# ERA-3SM.net
KiCad netlist of a schematic drawn in EAGLE
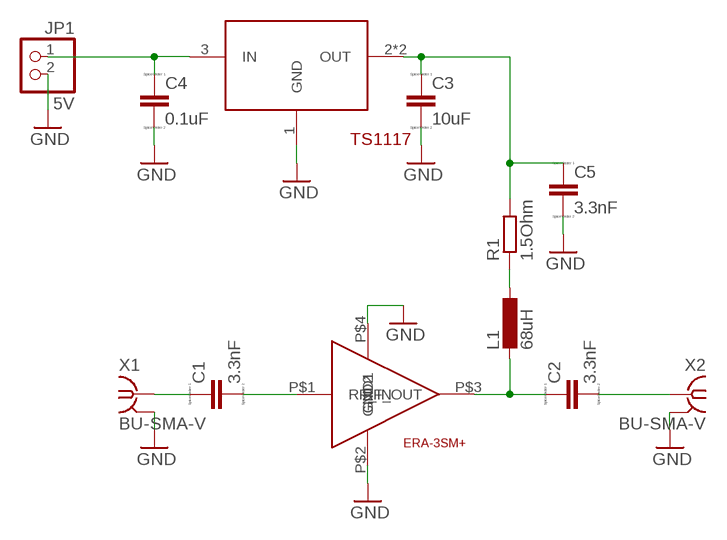
[diagram p0: schematic, sheet 1]

(export (version "E")
  (design (tool "Eeschema 10.0.6"))
  (components
    (comp (ref "C1")
      (value "3.3nF")
      (footprint "eagle-import:C0805")
      (libsource (lib "eagle-import") (part "C_SMD"))
    )
    (comp (ref "C2")
      (value "3.3nF")
      (footprint "eagle-import:C0805")
      (libsource (lib "eagle-import") (part "C_SMD"))
    )
    (comp (ref "C3")
      (value "10uF")
      (footprint "eagle-import:C0805")
      (libsource (lib "eagle-import") (part "C_SMD"))
    )
    (comp (ref "C4")
      (value "0.1uF")
      (footprint "eagle-import:C0805")
      (libsource (lib "eagle-import") (part "C_SMD"))
    )
    (comp (ref "C5")
      (value "3.3nF")
      (footprint "eagle-import:C0805")
      (libsource (lib "eagle-import") (part "C_SMD"))
    )
    (comp (ref "JP1")
      (value "5V")
      (footprint "eagle-import:1X02")
      (libsource (lib "eagle-import") (part "PINHD-1X2"))
    )
    (comp (ref "L1")
      (value "68uH")
      (footprint "eagle-import:1616FPS")
      (libsource (lib "eagle-import") (part "L-EU"))
    )
    (comp (ref "R1")
      (value "1.5Ohm")
      (footprint "eagle-import:R0805")
      (libsource (lib "eagle-import") (part "R-EU_R0805"))
    )
    (comp (ref "U$1")
      (value "ERA-3SM+")
      (footprint "eagle-import:WW107")
      (libsource (lib "eagle-import") (part "ERA-3SM+"))
    )
    (comp (ref "U$2")
      (value "TS1117")
      (footprint "eagle-import:SOT223")
      (libsource (lib "eagle-import") (part "TS1117"))
    )
    (comp (ref "X1")
      (value "BU-SMA-V")
      (footprint "eagle-import:BU-SMA-V")
      (libsource (lib "eagle-import") (part "BU-SMA-V"))
    )
    (comp (ref "X2")
      (value "BU-SMA-V")
      (footprint "eagle-import:BU-SMA-V")
      (libsource (lib "eagle-import") (part "BU-SMA-V"))
    )
  )
  (nets
    (net (code "1") (name "GND") (class "Default")
      (node (ref "C3") (pin "2") (pinfunction "2_2") (pintype "passive"))
      (node (ref "C4") (pin "2") (pinfunction "2_2") (pintype "passive"))
      (node (ref "C5") (pin "2") (pinfunction "2_2") (pintype "passive"))
      (node (ref "JP1") (pin "2") (pinfunction "2_2") (pintype "passive"))
      (node (ref "U$1") (pin "P$2") (pinfunction "GND1_P$2") (pintype "bidirectional"))
      (node (ref "U$1") (pin "P$4") (pinfunction "GND2_P$4") (pintype "bidirectional"))
      (node (ref "U$2") (pin "1") (pinfunction "GND_1") (pintype "bidirectional"))
      (node (ref "X1") (pin "2") (pinfunction "2_2") (pintype "passive"))
      (node (ref "X1") (pin "3") (pinfunction "2_3") (pintype "passive"))
      (node (ref "X1") (pin "4") (pinfunction "2_4") (pintype "passive"))
      (node (ref "X1") (pin "5") (pinfunction "2_5") (pintype "passive"))
      (node (ref "X2") (pin "2") (pinfunction "2_2") (pintype "passive"))
      (node (ref "X2") (pin "3") (pinfunction "2_3") (pintype "passive"))
      (node (ref "X2") (pin "4") (pinfunction "2_4") (pintype "passive"))
      (node (ref "X2") (pin "5") (pinfunction "2_5") (pintype "passive"))
    )
    (net (code "2") (name "Net-(C1-Pad1)") (class "Default")
      (node (ref "C1") (pin "1") (pinfunction "1_1") (pintype "passive"))
      (node (ref "X1") (pin "1") (pinfunction "1_1") (pintype "passive"))
    )
    (net (code "3") (name "Net-(C2-Pad2)") (class "Default")
      (node (ref "C2") (pin "2") (pinfunction "2_2") (pintype "passive"))
      (node (ref "X2") (pin "1") (pinfunction "1_1") (pintype "passive"))
    )
    (net (code "4") (name "Net-(C3-Pad1)") (class "Default")
      (node (ref "C3") (pin "1") (pinfunction "1_1") (pintype "passive"))
      (node (ref "C5") (pin "1") (pinfunction "1_1") (pintype "passive"))
      (node (ref "R1") (pin "2") (pinfunction "2_2") (pintype "passive"))
      (node (ref "U$2") (pin "2") (pinfunction "OUT_2") (pintype "bidirectional"))
      (node (ref "U$2") (pin "4") (pinfunction "OUT_4") (pintype "bidirectional"))
    )
    (net (code "5") (name "Net-(L1-1)") (class "Default")
      (node (ref "L1") (pin "P$1") (pinfunction "1_P$1") (pintype "passive"))
      (node (ref "R1") (pin "1") (pinfunction "1_1") (pintype "passive"))
    )
    (net (code "6") (name "Net-(L1-2)") (class "Default")
      (node (ref "C2") (pin "1") (pinfunction "1_1") (pintype "passive"))
      (node (ref "L1") (pin "P$2") (pinfunction "2_P$2") (pintype "passive"))
      (node (ref "U$1") (pin "P$3") (pinfunction "RF_OUT_P$3") (pintype "bidirectional"))
    )
    (net (code "7") (name "Net-(U$1-RF_IN)") (class "Default")
      (node (ref "C1") (pin "2") (pinfunction "2_2") (pintype "passive"))
      (node (ref "U$1") (pin "P$1") (pinfunction "RF_IN_P$1") (pintype "bidirectional"))
    )
    (net (code "8") (name "Net-(U$2-IN)") (class "Default")
      (node (ref "C4") (pin "1") (pinfunction "1_1") (pintype "passive"))
      (node (ref "JP1") (pin "1") (pinfunction "1_1") (pintype "passive"))
      (node (ref "U$2") (pin "3") (pinfunction "IN_3") (pintype "bidirectional"))
    )
  )
)
